# harp_behavior_poke_port_breakout_v2_0.net
KiCad netlist of a schematic drawn in EAGLE
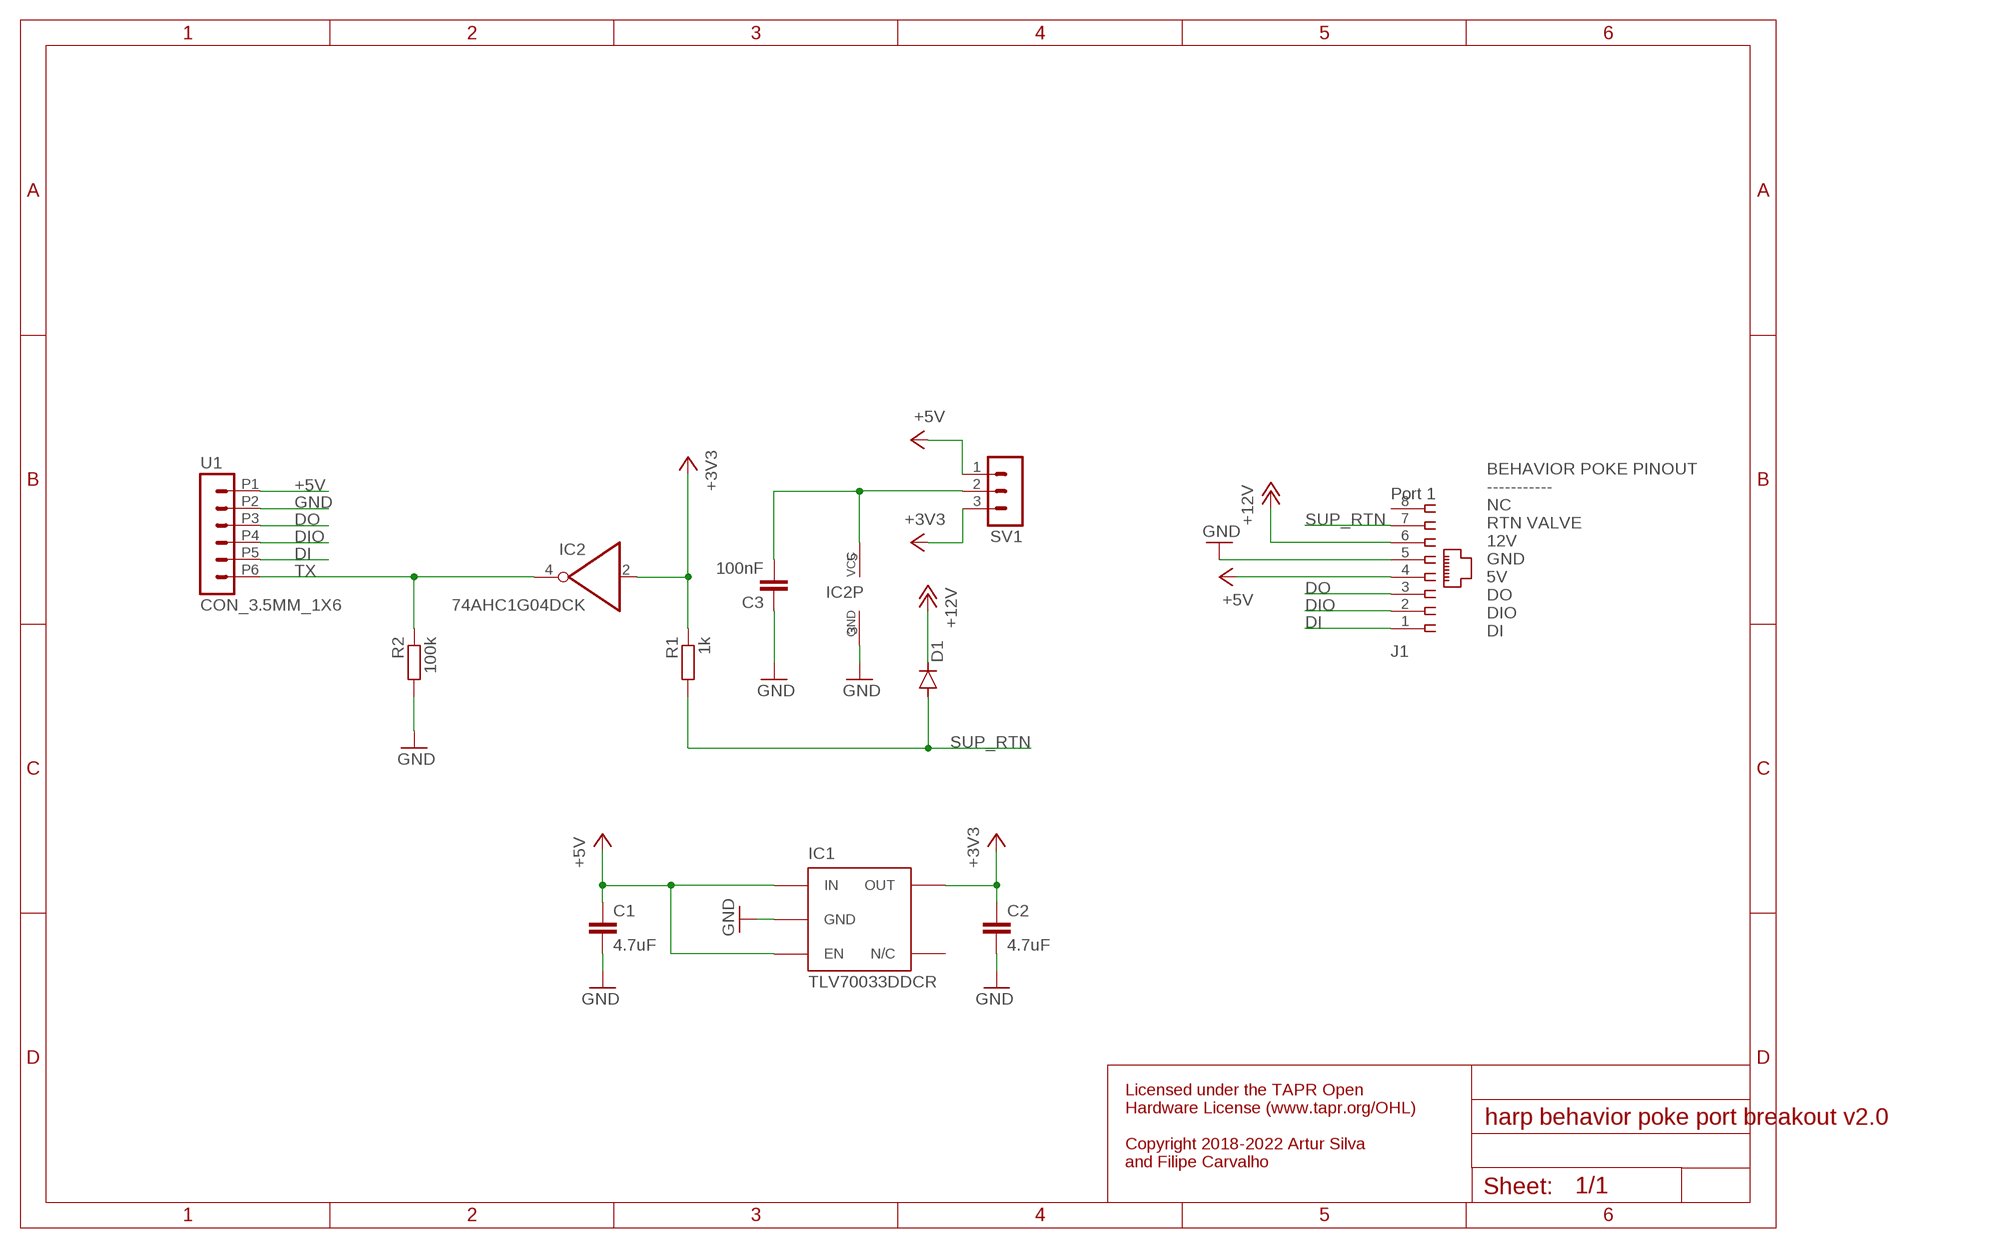
[diagram p0: schematic, sheet 1]

(export (version "E")
  (design (tool "Eeschema 10.0.6"))
  (components
    (comp (ref "C1")
      (value "4.7uF")
      (footprint "eagle-import:C0603")
      (libsource (lib "eagle-import") (part "C-EUC0603"))
    )
    (comp (ref "C2")
      (value "4.7uF")
      (footprint "eagle-import:C0603")
      (libsource (lib "eagle-import") (part "C-EUC0603"))
    )
    (comp (ref "C3")
      (value "100nF")
      (footprint "eagle-import:C0402")
      (libsource (lib "eagle-import") (part "C-EUC0402"))
    )
    (comp (ref "D1")
      (value "DIODE")
      (footprint "eagle-import:SOD-323-DIODE")
      (libsource (lib "eagle-import") (part "DIODE"))
    )
    (comp (ref "IC1")
      (value "TLV70033DDCR")
      (footprint "eagle-import:TSOT23-5")
      (libsource (lib "eagle-import") (part "TLV700XX"))
    )
    (comp (ref "IC2")
      (value "74AHC1G04DCK")
      (footprint "eagle-import:SC70-5")
      (libsource (lib "eagle-import") (part "741G04DCKAHC"))
    )
    (comp (ref "J1")
      (value "Port 1")
      (footprint "eagle-import:520426-4")
      (libsource (lib "eagle-import") (part "520426-4"))
    )
    (comp (ref "R1")
      (value "1k")
      (footprint "eagle-import:R0402")
      (libsource (lib "eagle-import") (part "R-EU_R0402"))
    )
    (comp (ref "R2")
      (value "100k")
      (footprint "eagle-import:R0402")
      (libsource (lib "eagle-import") (part "R-EU_R0402"))
    )
    (comp (ref "SV1")
      (value "MA03-1")
      (footprint "eagle-import:MA03-1")
      (libsource (lib "eagle-import") (part "MA03-1"))
    )
    (comp (ref "U1")
      (value "CON_3.5MM_1X6")
      (footprint "eagle-import:CON_3.5MM_1X6")
      (libsource (lib "eagle-import") (part "CON_3.5MM_1X6"))
    )
  )
  (nets
    (net (code "1") (name "+3V3") (class "Default")
      (node (ref "C2") (pin "1") (pinfunction "1_1") (pintype "passive"))
      (node (ref "IC1") (pin "5") (pinfunction "OUT_5") (pintype "bidirectional"))
      (node (ref "IC2") (pin "2") (pinfunction "I_2") (pintype "input"))
      (node (ref "R1") (pin "1") (pinfunction "1_1") (pintype "passive"))
      (node (ref "SV1") (pin "3") (pinfunction "3_3") (pintype "passive"))
    )
    (net (code "2") (name "+5V") (class "Default")
      (node (ref "C1") (pin "1") (pinfunction "1_1") (pintype "passive"))
      (node (ref "IC1") (pin "1") (pinfunction "IN_1") (pintype "bidirectional"))
      (node (ref "IC1") (pin "3") (pinfunction "EN_3") (pintype "bidirectional"))
      (node (ref "J1") (pin "4") (pinfunction "4_4") (pintype "passive"))
      (node (ref "SV1") (pin "1") (pinfunction "1_1") (pintype "passive"))
      (node (ref "U1") (pin "P1") (pinfunction "1_P1") (pintype "passive"))
    )
    (net (code "3") (name "+12V") (class "Default")
      (node (ref "D1") (pin "C") (pinfunction "C_C") (pintype "passive"))
      (node (ref "J1") (pin "6") (pinfunction "6_6") (pintype "passive"))
    )
    (net (code "4") (name "/DI") (class "Default")
      (node (ref "J1") (pin "1") (pinfunction "1_1") (pintype "passive"))
      (node (ref "U1") (pin "P5") (pinfunction "5_P5") (pintype "passive"))
    )
    (net (code "5") (name "/DIO") (class "Default")
      (node (ref "J1") (pin "2") (pinfunction "2_2") (pintype "passive"))
      (node (ref "U1") (pin "P4") (pinfunction "4_P4") (pintype "passive"))
    )
    (net (code "6") (name "/DO") (class "Default")
      (node (ref "J1") (pin "3") (pinfunction "3_3") (pintype "passive"))
      (node (ref "U1") (pin "P3") (pinfunction "3_P3") (pintype "passive"))
    )
    (net (code "7") (name "/SUP_RTN") (class "Default")
      (node (ref "D1") (pin "A") (pinfunction "A_A") (pintype "passive"))
      (node (ref "J1") (pin "7") (pinfunction "7_7") (pintype "passive"))
      (node (ref "R1") (pin "2") (pinfunction "2_2") (pintype "passive"))
    )
    (net (code "8") (name "/TX") (class "Default")
      (node (ref "IC2") (pin "4") (pinfunction "O_4") (pintype "output"))
      (node (ref "R2") (pin "1") (pinfunction "1_1") (pintype "passive"))
      (node (ref "U1") (pin "P6") (pinfunction "6_P6") (pintype "passive"))
    )
    (net (code "9") (name "GND") (class "Default")
      (node (ref "C1") (pin "2") (pinfunction "2_2") (pintype "passive"))
      (node (ref "C2") (pin "2") (pinfunction "2_2") (pintype "passive"))
      (node (ref "C3") (pin "1") (pinfunction "1_1") (pintype "passive"))
      (node (ref "IC1") (pin "2") (pinfunction "GND_2") (pintype "bidirectional"))
      (node (ref "IC2") (pin "3") (pinfunction "GND_3") (pintype "power_in"))
      (node (ref "J1") (pin "5") (pinfunction "5_5") (pintype "passive"))
      (node (ref "R2") (pin "2") (pinfunction "2_2") (pintype "passive"))
      (node (ref "U1") (pin "P2") (pinfunction "2_P2") (pintype "passive"))
    )
    (net (code "10") (name "Net-(IC2B-VCC)") (class "Default")
      (node (ref "C3") (pin "2") (pinfunction "2_2") (pintype "passive"))
      (node (ref "IC2") (pin "5") (pinfunction "VCC_5") (pintype "power_in"))
      (node (ref "SV1") (pin "2") (pinfunction "2_2") (pintype "passive"))
    )
    (net (code "11") (name "unconnected-(IC1-N{slash}C-Pad4)") (class "Default")
      (node (ref "IC1") (pin "4") (pinfunction "N/C_4") (pintype "bidirectional"))
    )
    (net (code "12") (name "unconnected-(J1-Pad8)") (class "Default")
      (node (ref "J1") (pin "8") (pinfunction "8_8") (pintype "passive"))
    )
  )
)
